# DeltaApply.net
KiCad netlist of a schematic drawn in EAGLE
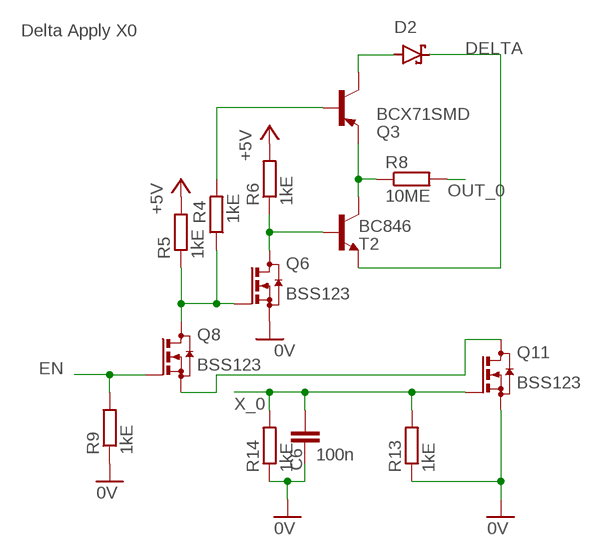
[diagram p0: schematic, sheet 1]

(export (version "E")
  (design (tool "Eeschema 10.0.6"))
  (components
    (comp (ref "C6")
      (value "100n")
      (footprint "eagle-import:C0805")
      (libsource (lib "eagle-import") (part "C-EUC0805"))
    )
    (comp (ref "D2")
      (value "BAT60J")
      (footprint "eagle-import:SOD323_ST")
      (libsource (lib "eagle-import") (part "BAT60J"))
    )
    (comp (ref "Q3")
      (value "BCX71SMD")
      (footprint "eagle-import:SOT23")
      (libsource (lib "eagle-import") (part "BCX71SMD"))
    )
    (comp (ref "Q6")
      (value "BSS123")
      (footprint "eagle-import:SOT23")
      (libsource (lib "eagle-import") (part "BSS123"))
    )
    (comp (ref "Q8")
      (value "BSS123")
      (footprint "eagle-import:SOT23")
      (libsource (lib "eagle-import") (part "BSS123"))
    )
    (comp (ref "Q11")
      (value "BSS123")
      (footprint "eagle-import:SOT23")
      (libsource (lib "eagle-import") (part "BSS123"))
    )
    (comp (ref "R4")
      (value "1kE")
      (footprint "eagle-import:M0805")
      (libsource (lib "eagle-import") (part "R-EU_M0805"))
    )
    (comp (ref "R5")
      (value "1kE")
      (footprint "eagle-import:M0805")
      (libsource (lib "eagle-import") (part "R-EU_M0805"))
    )
    (comp (ref "R6")
      (value "1kE")
      (footprint "eagle-import:M0805")
      (libsource (lib "eagle-import") (part "R-EU_M0805"))
    )
    (comp (ref "R8")
      (value "10ME")
      (footprint "eagle-import:M0805")
      (libsource (lib "eagle-import") (part "R-EU_M0805"))
    )
    (comp (ref "R9")
      (value "1kE")
      (footprint "eagle-import:M0805")
      (libsource (lib "eagle-import") (part "R-EU_M0805"))
    )
    (comp (ref "R13")
      (value "1kE")
      (footprint "eagle-import:M0805")
      (libsource (lib "eagle-import") (part "R-EU_M0805"))
    )
    (comp (ref "R14")
      (value "1kE")
      (footprint "eagle-import:M0805")
      (libsource (lib "eagle-import") (part "R-EU_M0805"))
    )
    (comp (ref "T2")
      (value "BC846")
      (footprint "eagle-import:SOT23")
      (libsource (lib "eagle-import") (part "BC846"))
    )
  )
  (nets
    (net (code "1") (name "+5V") (class "Default")
      (node (ref "R5") (pin "2") (pinfunction "2_2") (pintype "passive"))
      (node (ref "R6") (pin "2") (pinfunction "2_2") (pintype "passive"))
    )
    (net (code "2") (name "/DELTA") (class "Default")
      (node (ref "D2") (pin "C") (pinfunction "C_C") (pintype "passive"))
      (node (ref "T2") (pin "2") (pinfunction "E_2") (pintype "passive"))
    )
    (net (code "3") (name "/EN") (class "Default")
      (node (ref "Q8") (pin "1") (pinfunction "G_1") (pintype "passive"))
      (node (ref "R9") (pin "2") (pinfunction "2_2") (pintype "passive"))
    )
    (net (code "4") (name "/OUT_0") (class "Default")
      (node (ref "R8") (pin "2") (pinfunction "2_2") (pintype "passive"))
    )
    (net (code "5") (name "/X_0") (class "Default")
      (node (ref "C6") (pin "1") (pinfunction "1_1") (pintype "passive"))
      (node (ref "Q11") (pin "1") (pinfunction "G_1") (pintype "passive"))
      (node (ref "R13") (pin "2") (pinfunction "2_2") (pintype "passive"))
      (node (ref "R14") (pin "2") (pinfunction "2_2") (pintype "passive"))
    )
    (net (code "6") (name "0V") (class "Default")
      (node (ref "C6") (pin "2") (pinfunction "2_2") (pintype "passive"))
      (node (ref "Q11") (pin "2") (pinfunction "S_2") (pintype "passive"))
      (node (ref "Q6") (pin "2") (pinfunction "S_2") (pintype "passive"))
      (node (ref "R13") (pin "1") (pinfunction "1_1") (pintype "passive"))
      (node (ref "R14") (pin "1") (pinfunction "1_1") (pintype "passive"))
      (node (ref "R9") (pin "1") (pinfunction "1_1") (pintype "passive"))
    )
    (net (code "7") (name "Net-(Q3-B)") (class "Default")
      (node (ref "Q3") (pin "1") (pinfunction "B_1") (pintype "passive"))
      (node (ref "R4") (pin "2") (pinfunction "2_2") (pintype "passive"))
    )
    (net (code "8") (name "Net-(Q3-C)") (class "Default")
      (node (ref "D2") (pin "A") (pinfunction "A_A") (pintype "passive"))
      (node (ref "Q3") (pin "3") (pinfunction "C_3") (pintype "passive"))
    )
    (net (code "9") (name "Net-(Q3-E)") (class "Default")
      (node (ref "Q3") (pin "2") (pinfunction "E_2") (pintype "passive"))
      (node (ref "R8") (pin "1") (pinfunction "1_1") (pintype "passive"))
      (node (ref "T2") (pin "3") (pinfunction "C_3") (pintype "passive"))
    )
    (net (code "10") (name "Net-(Q6-D)") (class "Default")
      (node (ref "Q6") (pin "3") (pinfunction "D_3") (pintype "passive"))
      (node (ref "R6") (pin "1") (pinfunction "1_1") (pintype "passive"))
      (node (ref "T2") (pin "1") (pinfunction "B_1") (pintype "passive"))
    )
    (net (code "11") (name "Net-(Q6-G)") (class "Default")
      (node (ref "Q6") (pin "1") (pinfunction "G_1") (pintype "passive"))
      (node (ref "Q8") (pin "3") (pinfunction "D_3") (pintype "passive"))
      (node (ref "R4") (pin "1") (pinfunction "1_1") (pintype "passive"))
      (node (ref "R5") (pin "1") (pinfunction "1_1") (pintype "passive"))
    )
    (net (code "12") (name "Net-(Q11-D)") (class "Default")
      (node (ref "Q11") (pin "3") (pinfunction "D_3") (pintype "passive"))
      (node (ref "Q8") (pin "2") (pinfunction "S_2") (pintype "passive"))
    )
  )
)
